# power_dist.net
KiCad netlist of a schematic drawn in EAGLE
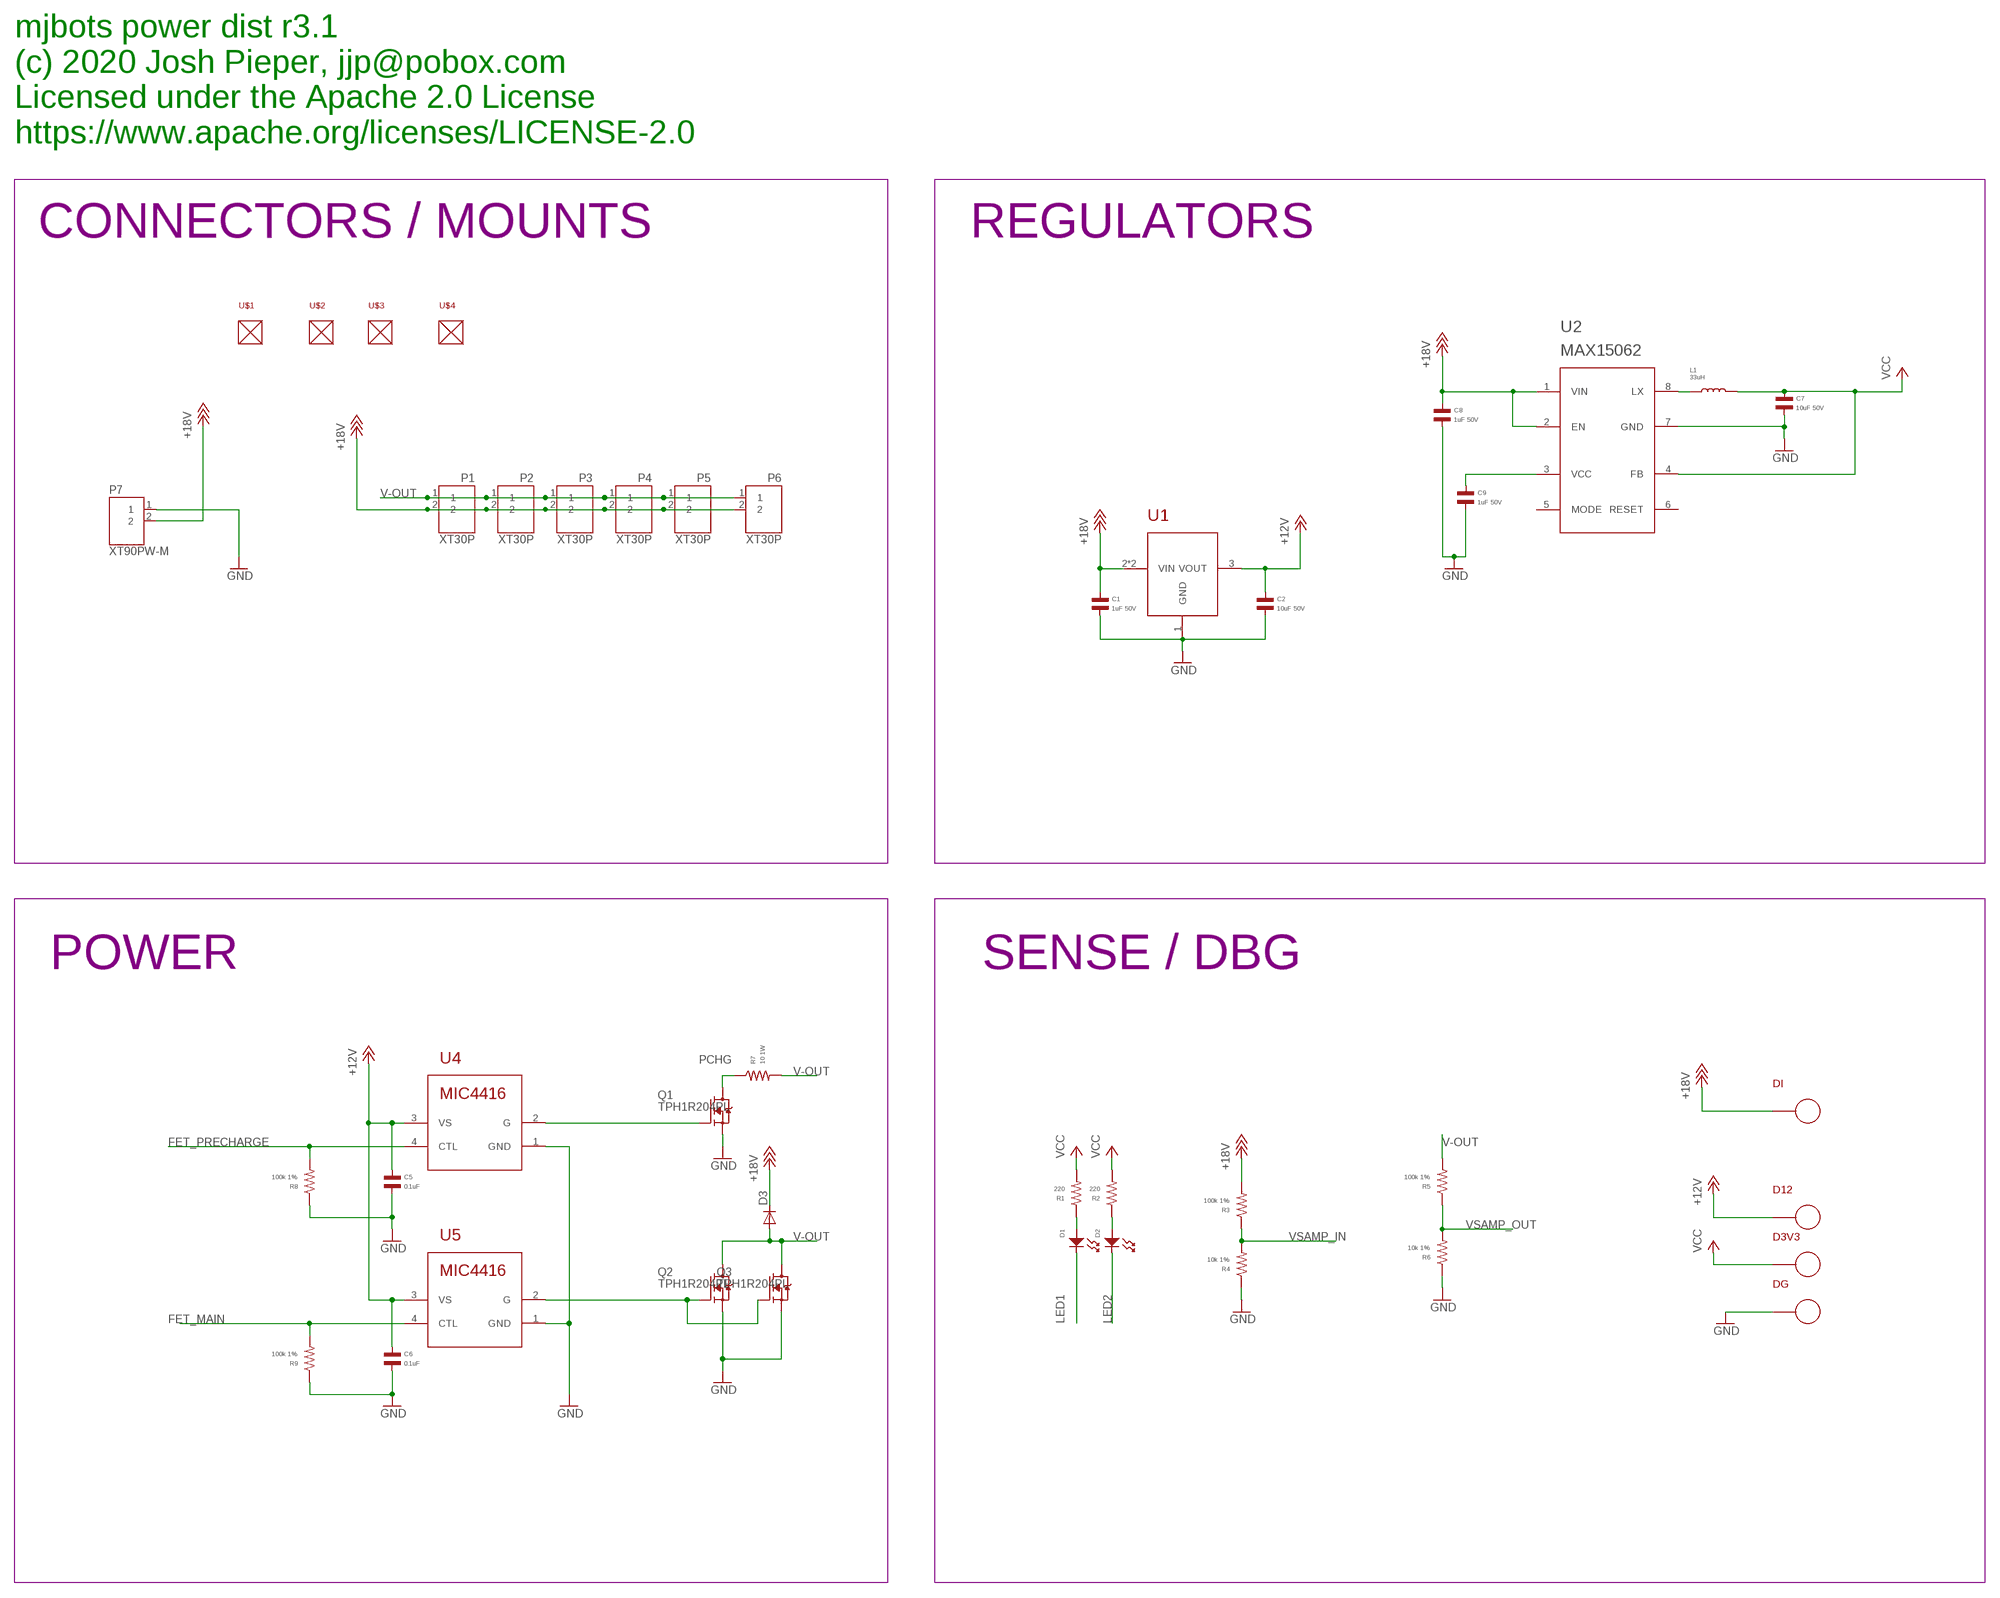
[diagram p0: schematic, sheet 1, part 1 of 2]
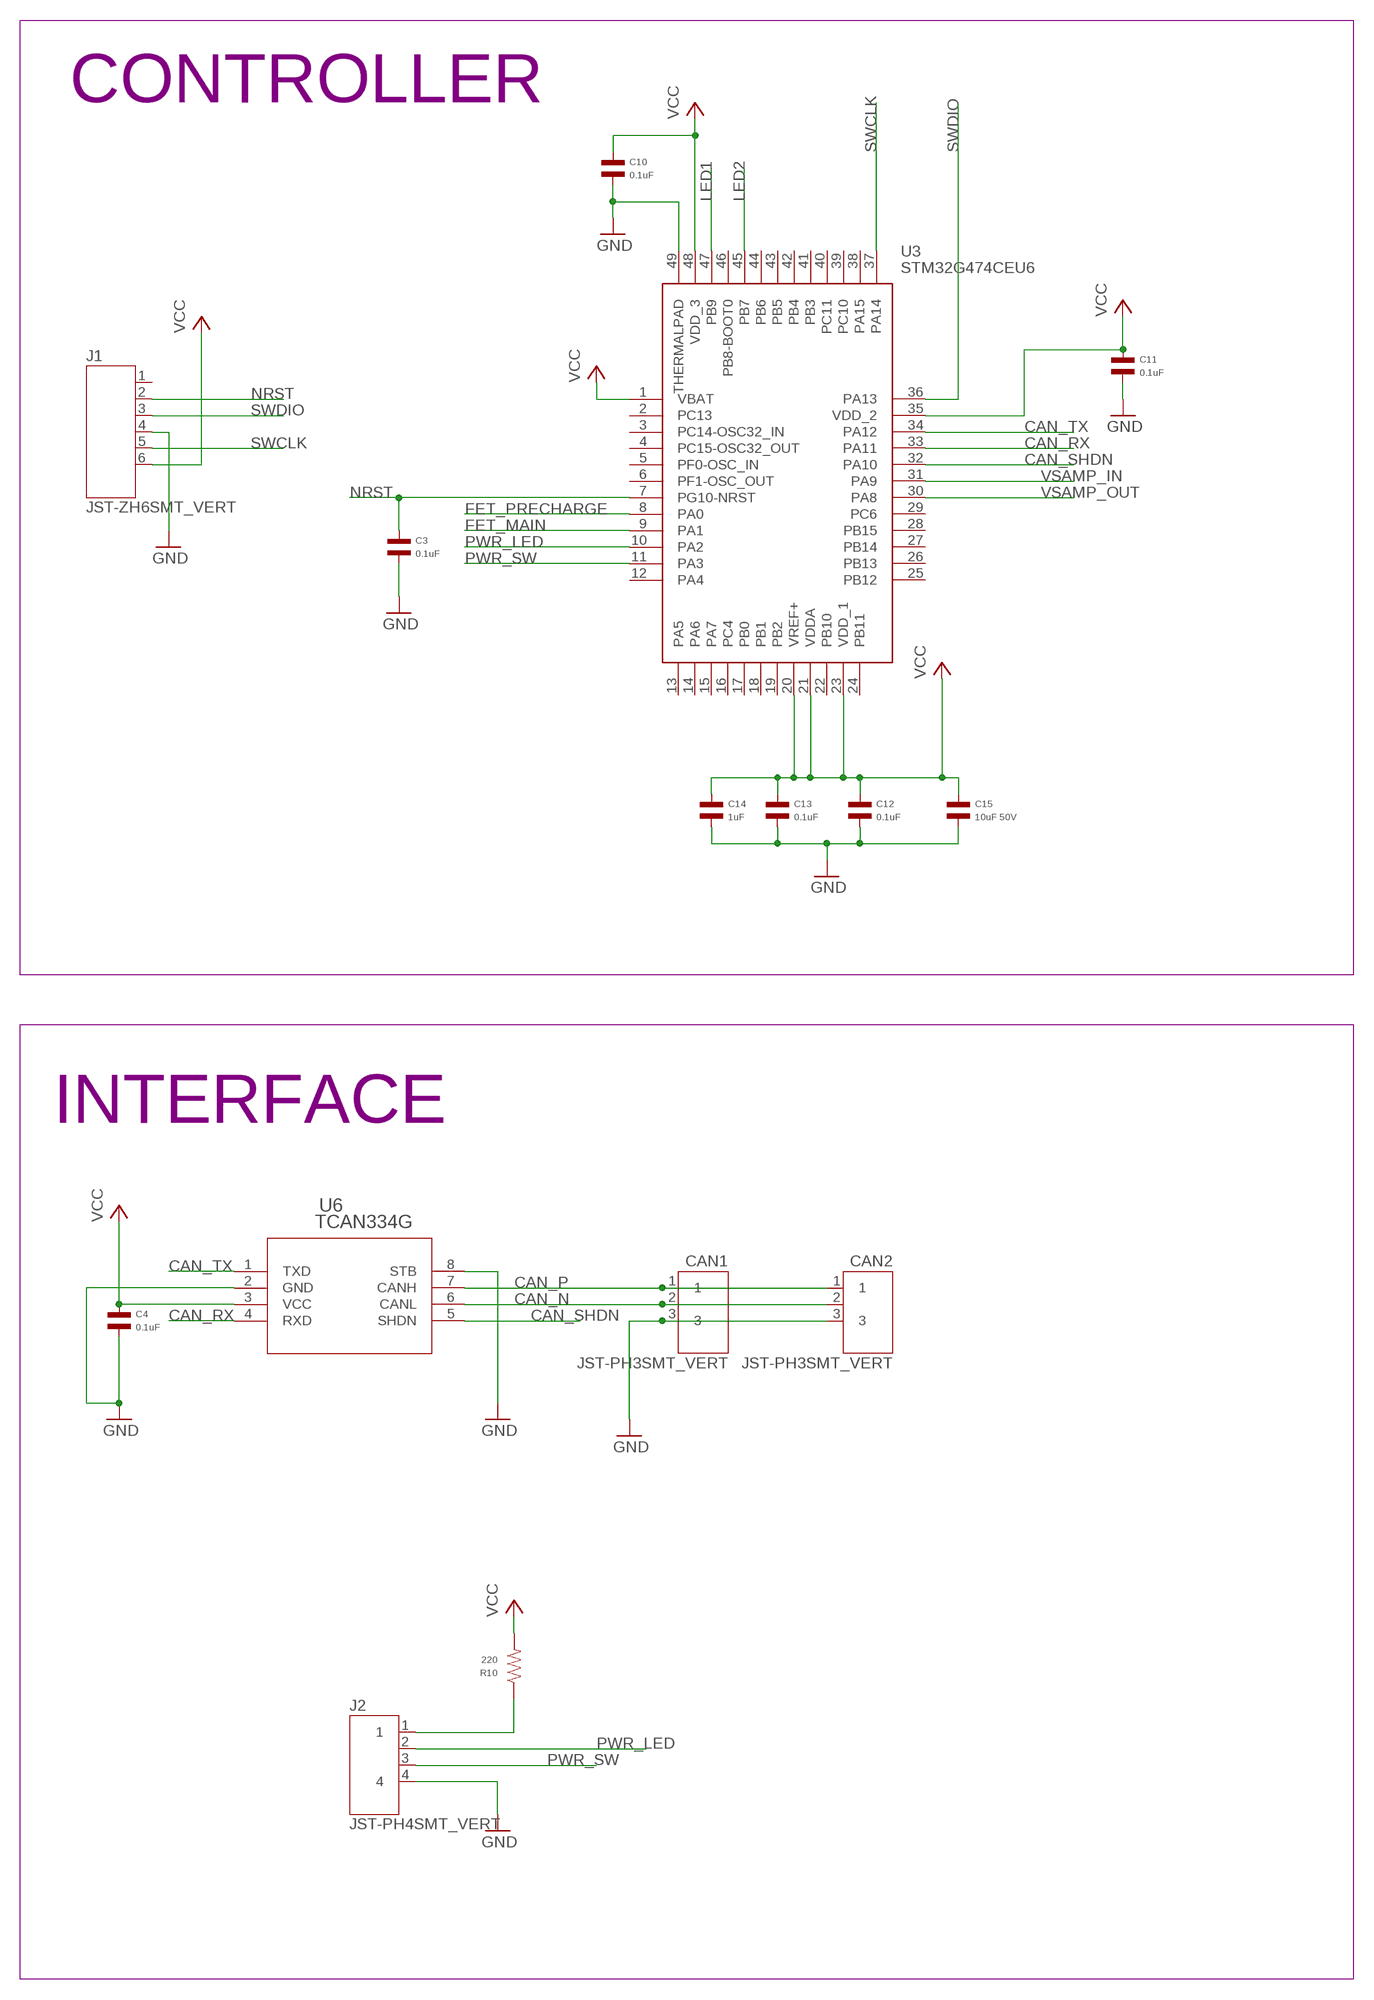
[diagram p1: schematic, sheet 1, part 2 of 2]

(export (version "E")
  (design (tool "Eeschema 10.0.6"))
  (components
    (comp (ref "C1")
      (value "1uF 50V")
      (footprint "eagle-import:C0603")
      (fields (field (name "MF") "SAMSUNG") (field (name "MPN") "CL10A105KB8NNNC"))
      (libsource (lib "eagle-import") (part "CAPACITOR_NP_0603"))
    )
    (comp (ref "C2")
      (value "10uF 50V")
      (footprint "eagle-import:C1206")
      (fields (field (name "MF") "TDK") (field (name "MPN") "C3216X7R1H106K160AE"))
      (libsource (lib "eagle-import") (part "CAPACITOR_NP_1206"))
    )
    (comp (ref "C3")
      (value "0.1uF")
      (footprint "eagle-import:C0402")
      (fields (field (name "HOUSEPART") "1") (field (name "MPN") "MF-CAP-0402-0.1uF"))
      (libsource (lib "eagle-import") (part "CAPACITOR_NP_0402"))
    )
    (comp (ref "C4")
      (value "0.1uF")
      (footprint "eagle-import:C0402")
      (fields (field (name "HOUSEPART") "1") (field (name "MPN") "MF-CAP-0402-0.1uF"))
      (libsource (lib "eagle-import") (part "CAPACITOR_NP_0402"))
    )
    (comp (ref "C5")
      (value "0.1uF")
      (footprint "eagle-import:C0402")
      (fields (field (name "HOUSEPART") "1") (field (name "MPN") "MF-CAP-0402-0.1uF"))
      (libsource (lib "eagle-import") (part "CAPACITOR_NP_0402"))
    )
    (comp (ref "C6")
      (value "0.1uF")
      (footprint "eagle-import:C0402")
      (fields (field (name "HOUSEPART") "1") (field (name "MPN") "MF-CAP-0402-0.1uF"))
      (libsource (lib "eagle-import") (part "CAPACITOR_NP_0402"))
    )
    (comp (ref "C7")
      (value "10uF 50V")
      (footprint "eagle-import:C1206")
      (fields (field (name "MF") "TDK") (field (name "MPN") "C3216X7R1H106K160AE"))
      (libsource (lib "eagle-import") (part "CAPACITOR_NP_1206"))
    )
    (comp (ref "C8")
      (value "1uF 50V")
      (footprint "eagle-import:C0603")
      (fields (field (name "MF") "SAMSUNG") (field (name "MPN") "CL10A105KB8NNNC"))
      (libsource (lib "eagle-import") (part "CAPACITOR_NP_0603"))
    )
    (comp (ref "C9")
      (value "1uF 50V")
      (footprint "eagle-import:C0603")
      (fields (field (name "MF") "SAMSUNG") (field (name "MPN") "CL10A105KB8NNNC"))
      (libsource (lib "eagle-import") (part "CAPACITOR_NP_0603"))
    )
    (comp (ref "C10")
      (value "0.1uF")
      (footprint "eagle-import:C0402")
      (fields (field (name "HOUSEPART") "1") (field (name "MPN") "MF-CAP-0402-0.1uF"))
      (libsource (lib "eagle-import") (part "CAPACITOR_NP_0402"))
    )
    (comp (ref "C11")
      (value "0.1uF")
      (footprint "eagle-import:C0402")
      (fields (field (name "HOUSEPART") "1") (field (name "MPN") "MF-CAP-0402-0.1uF"))
      (libsource (lib "eagle-import") (part "CAPACITOR_NP_0402"))
    )
    (comp (ref "C12")
      (value "0.1uF")
      (footprint "eagle-import:C0402")
      (fields (field (name "HOUSEPART") "1") (field (name "MPN") "MF-CAP-0402-0.1uF"))
      (libsource (lib "eagle-import") (part "CAPACITOR_NP_0402"))
    )
    (comp (ref "C13")
      (value "0.1uF")
      (footprint "eagle-import:C0402")
      (fields (field (name "HOUSEPART") "1") (field (name "MPN") "MF-CAP-0402-0.1uF"))
      (libsource (lib "eagle-import") (part "CAPACITOR_NP_0402"))
    )
    (comp (ref "C14")
      (value "1uF")
      (footprint "eagle-import:C0402")
      (fields (field (name "HOUSEPART") "1") (field (name "MPN") "MF-CAP-0402-1uF"))
      (libsource (lib "eagle-import") (part "CAPACITOR_NP_0402"))
    )
    (comp (ref "C15")
      (value "10uF 50V")
      (footprint "eagle-import:C1206")
      (fields (field (name "MF") "TDK") (field (name "MPN") "C3216X7R1H106K160AE"))
      (libsource (lib "eagle-import") (part "CAPACITOR_NP_1206"))
    )
    (comp (ref "CAN1")
      (value "JST-PH3SMT_VERT")
      (footprint "eagle-import:JST_B3B_PH-SM4-TB(LF)(SN)")
      (fields (field (name "MF") "JST") (field (name "MPN") "B3B-PH-SM4-TB(LF)(SN)"))
      (libsource (lib "eagle-import") (part "JST-PH3SMT_VERT"))
    )
    (comp (ref "CAN2")
      (value "JST-PH3SMT_VERT")
      (footprint "eagle-import:JST_B3B_PH-SM4-TB(LF)(SN)")
      (fields (field (name "MF") "JST") (field (name "MPN") "B3B-PH-SM4-TB(LF)(SN)"))
      (libsource (lib "eagle-import") (part "JST-PH3SMT_VERT"))
    )
    (comp (ref "D1")
      (value "LED_SINGLE-0603")
      (footprint "eagle-import:LED0603")
      (fields
        (field (name "HOUSEPART") "NO")
        (field (name "HOUSEPART_1") "1")
        (field (name "MPN") "MF-LED-0603-RED")
      )
      (libsource (lib "eagle-import") (part "LED_SINGLE-0603"))
    )
    (comp (ref "D2")
      (value "LED_SINGLE-0603")
      (footprint "eagle-import:LED0603")
      (fields
        (field (name "HOUSEPART") "NO")
        (field (name "HOUSEPART_1") "1")
        (field (name "MPN") "MF-LED-0603-RED")
      )
      (libsource (lib "eagle-import") (part "LED_SINGLE-0603"))
    )
    (comp (ref "D3")
      (value "DIODE-")
      (footprint "eagle-import:DO-214AB")
      (fields (field (name "MF") "MICRO COMMERCIAL") (field (name "MPN") "SK510L-TP"))
      (libsource (lib "eagle-import") (part "DIODE-"))
    )
    (comp (ref "D3V3")
      (value "PAD24AWG_PAD")
      (footprint "eagle-import:24AWG_PAD")
      (libsource (lib "eagle-import") (part "PAD24AWG_PAD"))
    )
    (comp (ref "D12")
      (value "PAD24AWG_PAD")
      (footprint "eagle-import:24AWG_PAD")
      (libsource (lib "eagle-import") (part "PAD24AWG_PAD"))
    )
    (comp (ref "DG")
      (value "PAD24AWG_PAD")
      (footprint "eagle-import:24AWG_PAD")
      (libsource (lib "eagle-import") (part "PAD24AWG_PAD"))
    )
    (comp (ref "DI")
      (value "PAD24AWG_PAD")
      (footprint "eagle-import:24AWG_PAD")
      (libsource (lib "eagle-import") (part "PAD24AWG_PAD"))
    )
    (comp (ref "J1")
      (value "JST-ZH6SMT_VERT")
      (footprint "eagle-import:JST_B6B-ZR-SM4-TF(LF)(SN)")
      (fields (field (name "MF") "JST") (field (name "MPN") "B6B-ZR-SM4-TF(LF)(SN)"))
      (libsource (lib "eagle-import") (part "JST-ZH6SMT_VERT"))
    )
    (comp (ref "J2")
      (value "JST-PH4SMT_VERT")
      (footprint "eagle-import:JST_B4B_PH-SM4-TB(LF)(SN)")
      (fields (field (name "MF") "JST") (field (name "MPN") "B4B-PH-SM4-TB(LF)(SN)"))
      (libsource (lib "eagle-import") (part "JST-PH4SMT_VERT"))
    )
    (comp (ref "L1")
      (value "33uH")
      (footprint "eagle-import:L1210")
      (fields (field (name "MF") "TDK") (field (name "MPN") "NLFV32T-330K-EF") (field (name "POPULATE") "1"))
      (libsource (lib "eagle-import") (part "INDUCTOR_1210"))
    )
    (comp (ref "P1")
      (value "XT30P")
      (footprint "eagle-import:XT30P")
      (libsource (lib "eagle-import") (part "XT30P"))
    )
    (comp (ref "P2")
      (value "XT30P")
      (footprint "eagle-import:XT30P")
      (libsource (lib "eagle-import") (part "XT30P"))
    )
    (comp (ref "P3")
      (value "XT30P")
      (footprint "eagle-import:XT30P")
      (libsource (lib "eagle-import") (part "XT30P"))
    )
    (comp (ref "P4")
      (value "XT30P")
      (footprint "eagle-import:XT30P")
      (libsource (lib "eagle-import") (part "XT30P"))
    )
    (comp (ref "P5")
      (value "XT30P")
      (footprint "eagle-import:XT30P")
      (libsource (lib "eagle-import") (part "XT30P"))
    )
    (comp (ref "P6")
      (value "XT30P")
      (footprint "eagle-import:XT30P")
      (libsource (lib "eagle-import") (part "XT30P"))
    )
    (comp (ref "P7")
      (value "XT90PW-M")
      (footprint "eagle-import:XT90PW-M")
      (libsource (lib "eagle-import") (part "XT90PW-M"))
    )
    (comp (ref "Q1")
      (value "TPH1R204PL")
      (footprint "eagle-import:SOP_ADVANCE")
      (fields (field (name "MF") "Toshiba") (field (name "MPN") "TPH1R204PL,L1Q"))
      (libsource (lib "eagle-import") (part "TPH1R204PL"))
    )
    (comp (ref "Q2")
      (value "TPH1R204PL")
      (footprint "eagle-import:SOP_ADVANCE")
      (fields (field (name "MF") "Toshiba") (field (name "MPN") "TPH1R204PL,L1Q"))
      (libsource (lib "eagle-import") (part "TPH1R204PL"))
    )
    (comp (ref "Q3")
      (value "TPH1R204PL")
      (footprint "eagle-import:SOP_ADVANCE")
      (fields (field (name "MF") "Toshiba") (field (name "MPN") "TPH1R204PL,L1Q"))
      (libsource (lib "eagle-import") (part "TPH1R204PL"))
    )
    (comp (ref "R1")
      (value "220")
      (footprint "eagle-import:R0603")
      (fields (field (name "HOUSEPART") "1") (field (name "MPN") "MF-RES-0603-220"))
      (libsource (lib "eagle-import") (part "RESISTOR_0603"))
    )
    (comp (ref "R2")
      (value "220")
      (footprint "eagle-import:R0603")
      (fields (field (name "HOUSEPART") "1") (field (name "MPN") "MF-RES-0603-220"))
      (libsource (lib "eagle-import") (part "RESISTOR_0603"))
    )
    (comp (ref "R3")
      (value "100k 1%")
      (footprint "eagle-import:R0603")
      (fields (field (name "MF") "VISHAY") (field (name "MPN") "CRCW0603100KFKEA"))
      (libsource (lib "eagle-import") (part "RESISTOR_0603"))
    )
    (comp (ref "R4")
      (value "10k 1%")
      (footprint "eagle-import:R0603")
      (fields (field (name "MF") "PANASONIC") (field (name "MPN") "ERJ-3EKF1002V"))
      (libsource (lib "eagle-import") (part "RESISTOR_0603"))
    )
    (comp (ref "R5")
      (value "100k 1%")
      (footprint "eagle-import:R0603")
      (fields (field (name "MF") "VISHAY") (field (name "MPN") "CRCW0603100KFKEA"))
      (libsource (lib "eagle-import") (part "RESISTOR_0603"))
    )
    (comp (ref "R6")
      (value "10k 1%")
      (footprint "eagle-import:R0603")
      (fields (field (name "MF") "PANASONIC") (field (name "MPN") "ERJ-3EKF1002V"))
      (libsource (lib "eagle-import") (part "RESISTOR_0603"))
    )
    (comp (ref "R7")
      (value "10 1W")
      (footprint "eagle-import:R1206")
      (fields (field (name "MF") "Susumu") (field (name "MPN") "HRG3216Q-10R0-D-T1"))
      (libsource (lib "eagle-import") (part "RESISTOR_1206"))
    )
    (comp (ref "R8")
      (value "100k 1%")
      (footprint "eagle-import:R0603")
      (fields (field (name "MF") "VISHAY") (field (name "MPN") "CRCW0603100KFKEA"))
      (libsource (lib "eagle-import") (part "RESISTOR_0603"))
    )
    (comp (ref "R9")
      (value "100k 1%")
      (footprint "eagle-import:R0603")
      (fields (field (name "MF") "VISHAY") (field (name "MPN") "CRCW0603100KFKEA"))
      (libsource (lib "eagle-import") (part "RESISTOR_0603"))
    )
    (comp (ref "R10")
      (value "220")
      (footprint "eagle-import:R0603")
      (fields (field (name "HOUSEPART") "1") (field (name "MPN") "MF-RES-0603-220"))
      (libsource (lib "eagle-import") (part "RESISTOR_0603"))
    )
    (comp (ref "U$1")
      (value "MOUNT")
      (footprint "eagle-import:M2.5MOUNT")
      (libsource (lib "eagle-import") (part "MOUNT"))
    )
    (comp (ref "U$2")
      (value "MOUNT")
      (footprint "eagle-import:M2.5MOUNT")
      (libsource (lib "eagle-import") (part "MOUNT"))
    )
    (comp (ref "U$3")
      (value "MOUNT")
      (footprint "eagle-import:M2.5MOUNT")
      (libsource (lib "eagle-import") (part "MOUNT"))
    )
    (comp (ref "U$4")
      (value "MOUNT")
      (footprint "eagle-import:M2.5MOUNT")
      (libsource (lib "eagle-import") (part "MOUNT"))
    )
    (comp (ref "U1")
      (value "ZXTR2012Z")
      (footprint "eagle-import:SOT89")
      (fields (field (name "MF") "DIODES INC") (field (name "MPN") "ZXTR2012Z-13"))
      (libsource (lib "eagle-import") (part "ZXTR2012Z"))
    )
    (comp (ref "U2")
      (value "MAX150628TDFN")
      (footprint "eagle-import:8TDFN")
      (fields (field (name "MF") "MAXIM") (field (name "MPN") "MAX15062AATA+T"))
      (libsource (lib "eagle-import") (part "MAX150628TDFN"))
    )
    (comp (ref "U3")
      (value "STM32G474CEU6")
      (footprint "eagle-import:QFN50P700X700X60-49N")
      (fields (field (name "MOUSER_PART_NUMBER") "511-STM32G474CEU6") (field (name "MF") "ST"))
      (libsource (lib "eagle-import") (part "STM32G474CEU6"))
    )
    (comp (ref "U4")
      (value "MIC4416")
      (footprint "eagle-import:SOT143")
      (fields (field (name "MF") "MICROCHIP") (field (name "MPN") "MIC4416YM4-TR"))
      (libsource (lib "eagle-import") (part "MIC4416"))
    )
    (comp (ref "U5")
      (value "MIC4416")
      (footprint "eagle-import:SOT143")
      (fields (field (name "MF") "MICROCHIP") (field (name "MPN") "MIC4416YM4-TR"))
      (libsource (lib "eagle-import") (part "MIC4416"))
    )
    (comp (ref "U6")
      (value "TCAN334G")
      (footprint "eagle-import:SOIC8")
      (fields (field (name "MF") "Analog") (field (name "MPN") "LTC2875IS8"))
      (libsource (lib "eagle-import") (part "TCAN334G"))
    )
  )
  (nets
    (net (code "1") (name "+12V") (class "Default")
      (node (ref "C2") (pin "P$1") (pinfunction "P$1_P$1") (pintype "passive"))
      (node (ref "C5") (pin "P$1") (pinfunction "P$1_P$1") (pintype "passive"))
      (node (ref "C6") (pin "P$1") (pinfunction "P$1_P$1") (pintype "passive"))
      (node (ref "D12") (pin "P$1") (pinfunction "P$1_P$1") (pintype "bidirectional"))
      (node (ref "U1") (pin "3") (pinfunction "VOUT_3") (pintype "bidirectional"))
      (node (ref "U4") (pin "3") (pinfunction "VS_3") (pintype "bidirectional"))
      (node (ref "U5") (pin "3") (pinfunction "VS_3") (pintype "bidirectional"))
    )
    (net (code "2") (name "+18V") (class "Default")
      (node (ref "C1") (pin "P$1") (pinfunction "P$1_P$1") (pintype "passive"))
      (node (ref "C8") (pin "P$1") (pinfunction "P$1_P$1") (pintype "passive"))
      (node (ref "D3") (pin "C") (pinfunction "C_C") (pintype "passive"))
      (node (ref "DI") (pin "P$1") (pinfunction "P$1_P$1") (pintype "bidirectional"))
      (node (ref "P1") (pin "2") (pinfunction "2_2") (pintype "passive"))
      (node (ref "P2") (pin "2") (pinfunction "2_2") (pintype "passive"))
      (node (ref "P3") (pin "2") (pinfunction "2_2") (pintype "passive"))
      (node (ref "P4") (pin "2") (pinfunction "2_2") (pintype "passive"))
      (node (ref "P5") (pin "2") (pinfunction "2_2") (pintype "passive"))
      (node (ref "P6") (pin "2") (pinfunction "2_2") (pintype "passive"))
      (node (ref "P7") (pin "2") (pinfunction "2_2") (pintype "passive"))
      (node (ref "R3") (pin "P$2") (pinfunction "P$2_P$2") (pintype "passive"))
      (node (ref "U1") (pin "2") (pinfunction "VIN_2") (pintype "bidirectional"))
      (node (ref "U1") (pin "PAD") (pinfunction "VIN_PAD") (pintype "bidirectional"))
      (node (ref "U2") (pin "1") (pinfunction "VIN_1") (pintype "passive"))
      (node (ref "U2") (pin "2") (pinfunction "EN_2") (pintype "passive"))
    )
    (net (code "3") (name "/CAN_N") (class "Default")
      (node (ref "CAN1") (pin "2") (pinfunction "2_2") (pintype "passive"))
      (node (ref "CAN2") (pin "2") (pinfunction "2_2") (pintype "passive"))
      (node (ref "U6") (pin "6") (pinfunction "CANL_6") (pintype "bidirectional"))
    )
    (net (code "4") (name "/CAN_P") (class "Default")
      (node (ref "CAN1") (pin "1") (pinfunction "1_1") (pintype "passive"))
      (node (ref "CAN2") (pin "1") (pinfunction "1_1") (pintype "passive"))
      (node (ref "U6") (pin "7") (pinfunction "CANH_7") (pintype "bidirectional"))
    )
    (net (code "5") (name "/CAN_RX") (class "Default")
      (node (ref "U3") (pin "33") (pinfunction "PA11_33") (pintype "bidirectional"))
      (node (ref "U6") (pin "4") (pinfunction "RXD_4") (pintype "output"))
    )
    (net (code "6") (name "/CAN_SHDN") (class "Default")
      (node (ref "U3") (pin "32") (pinfunction "PA10_32") (pintype "bidirectional"))
      (node (ref "U6") (pin "5") (pinfunction "SHDN_5") (pintype "input"))
    )
    (net (code "7") (name "/CAN_TX") (class "Default")
      (node (ref "U3") (pin "34") (pinfunction "PA12_34") (pintype "bidirectional"))
      (node (ref "U6") (pin "1") (pinfunction "TXD_1") (pintype "input"))
    )
    (net (code "8") (name "/FET_MAIN") (class "Default")
      (node (ref "R9") (pin "P$2") (pinfunction "P$2_P$2") (pintype "passive"))
      (node (ref "U3") (pin "9") (pinfunction "PA1_9") (pintype "bidirectional"))
      (node (ref "U5") (pin "4") (pinfunction "CTL_4") (pintype "bidirectional"))
    )
    (net (code "9") (name "/FET_PRECHARGE") (class "Default")
      (node (ref "R8") (pin "P$2") (pinfunction "P$2_P$2") (pintype "passive"))
      (node (ref "U3") (pin "8") (pinfunction "PA0_8") (pintype "bidirectional"))
      (node (ref "U4") (pin "4") (pinfunction "CTL_4") (pintype "bidirectional"))
    )
    (net (code "10") (name "/LED1") (class "Default")
      (node (ref "D1") (pin "CATHODE") (pinfunction "CATHODE_CATHODE") (pintype "power_in"))
      (node (ref "U3") (pin "47") (pinfunction "PB9_47") (pintype "bidirectional"))
    )
    (net (code "11") (name "/LED2") (class "Default")
      (node (ref "D2") (pin "CATHODE") (pinfunction "CATHODE_CATHODE") (pintype "power_in"))
      (node (ref "U3") (pin "45") (pinfunction "PB7_45") (pintype "bidirectional"))
    )
    (net (code "12") (name "/NRST") (class "Default")
      (node (ref "C3") (pin "P$1") (pinfunction "P$1_P$1") (pintype "passive"))
      (node (ref "J1") (pin "2") (pinfunction "2_2") (pintype "passive"))
      (node (ref "U3") (pin "7") (pinfunction "PG10-NRST_7") (pintype "bidirectional"))
    )
    (net (code "13") (name "/PCHG") (class "Default")
      (node (ref "Q1") (pin "5") (pinfunction "D_5") (pintype "passive"))
      (node (ref "Q1") (pin "6") (pinfunction "D_6") (pintype "passive"))
      (node (ref "Q1") (pin "7") (pinfunction "D_7") (pintype "passive"))
      (node (ref "Q1") (pin "8") (pinfunction "D_8") (pintype "passive"))
      (node (ref "Q1") (pin "PAD") (pinfunction "D_PAD") (pintype "passive"))
      (node (ref "R7") (pin "P$1") (pinfunction "P$1_P$1") (pintype "passive"))
    )
    (net (code "14") (name "/PWR_LED") (class "Default")
      (node (ref "J2") (pin "2") (pinfunction "2_2") (pintype "passive"))
      (node (ref "U3") (pin "10") (pinfunction "PA2_10") (pintype "bidirectional"))
    )
    (net (code "15") (name "/PWR_SW") (class "Default")
      (node (ref "J2") (pin "3") (pinfunction "3_3") (pintype "passive"))
      (node (ref "U3") (pin "11") (pinfunction "PA3_11") (pintype "bidirectional"))
    )
    (net (code "16") (name "/SWCLK") (class "Default")
      (node (ref "J1") (pin "5") (pinfunction "5_5") (pintype "passive"))
      (node (ref "U3") (pin "37") (pinfunction "PA14_37") (pintype "bidirectional"))
    )
    (net (code "17") (name "/SWDIO") (class "Default")
      (node (ref "J1") (pin "3") (pinfunction "3_3") (pintype "passive"))
      (node (ref "U3") (pin "36") (pinfunction "PA13_36") (pintype "bidirectional"))
    )
    (net (code "18") (name "/V-OUT") (class "Default")
      (node (ref "D3") (pin "A") (pinfunction "A_A") (pintype "passive"))
      (node (ref "P1") (pin "1") (pinfunction "1_1") (pintype "passive"))
      (node (ref "P2") (pin "1") (pinfunction "1_1") (pintype "passive"))
      (node (ref "P3") (pin "1") (pinfunction "1_1") (pintype "passive"))
      (node (ref "P4") (pin "1") (pinfunction "1_1") (pintype "passive"))
      (node (ref "P5") (pin "1") (pinfunction "1_1") (pintype "passive"))
      (node (ref "P6") (pin "1") (pinfunction "1_1") (pintype "passive"))
      (node (ref "Q2") (pin "5") (pinfunction "D_5") (pintype "passive"))
      (node (ref "Q2") (pin "6") (pinfunction "D_6") (pintype "passive"))
      (node (ref "Q2") (pin "7") (pinfunction "D_7") (pintype "passive"))
      (node (ref "Q2") (pin "8") (pinfunction "D_8") (pintype "passive"))
      (node (ref "Q2") (pin "PAD") (pinfunction "D_PAD") (pintype "passive"))
      (node (ref "Q3") (pin "5") (pinfunction "D_5") (pintype "passive"))
      (node (ref "Q3") (pin "6") (pinfunction "D_6") (pintype "passive"))
      (node (ref "Q3") (pin "7") (pinfunction "D_7") (pintype "passive"))
      (node (ref "Q3") (pin "8") (pinfunction "D_8") (pintype "passive"))
      (node (ref "Q3") (pin "PAD") (pinfunction "D_PAD") (pintype "passive"))
      (node (ref "R5") (pin "P$2") (pinfunction "P$2_P$2") (pintype "passive"))
      (node (ref "R7") (pin "P$2") (pinfunction "P$2_P$2") (pintype "passive"))
    )
    (net (code "19") (name "/VSAMP_IN") (class "Default")
      (node (ref "R3") (pin "P$1") (pinfunction "P$1_P$1") (pintype "passive"))
      (node (ref "R4") (pin "P$2") (pinfunction "P$2_P$2") (pintype "passive"))
      (node (ref "U3") (pin "31") (pinfunction "PA9_31") (pintype "bidirectional"))
    )
    (net (code "20") (name "/VSAMP_OUT") (class "Default")
      (node (ref "R5") (pin "P$1") (pinfunction "P$1_P$1") (pintype "passive"))
      (node (ref "R6") (pin "P$2") (pinfunction "P$2_P$2") (pintype "passive"))
      (node (ref "U3") (pin "30") (pinfunction "PA8_30") (pintype "bidirectional"))
    )
    (net (code "21") (name "GND") (class "Default")
      (node (ref "C1") (pin "P$2") (pinfunction "P$2_P$2") (pintype "passive"))
      (node (ref "C10") (pin "P$2") (pinfunction "P$2_P$2") (pintype "passive"))
      (node (ref "C11") (pin "P$2") (pinfunction "P$2_P$2") (pintype "passive"))
      (node (ref "C12") (pin "P$2") (pinfunction "P$2_P$2") (pintype "passive"))
      (node (ref "C13") (pin "P$2") (pinfunction "P$2_P$2") (pintype "passive"))
      (node (ref "C14") (pin "P$2") (pinfunction "P$2_P$2") (pintype "passive"))
      (node (ref "C15") (pin "P$2") (pinfunction "P$2_P$2") (pintype "passive"))
      (node (ref "C2") (pin "P$2") (pinfunction "P$2_P$2") (pintype "passive"))
      (node (ref "C3") (pin "P$2") (pinfunction "P$2_P$2") (pintype "passive"))
      (node (ref "C4") (pin "P$2") (pinfunction "P$2_P$2") (pintype "passive"))
      (node (ref "C5") (pin "P$2") (pinfunction "P$2_P$2") (pintype "passive"))
      (node (ref "C6") (pin "P$2") (pinfunction "P$2_P$2") (pintype "passive"))
      (node (ref "C7") (pin "P$2") (pinfunction "P$2_P$2") (pintype "passive"))
      (node (ref "C8") (pin "P$2") (pinfunction "P$2_P$2") (pintype "passive"))
      (node (ref "C9") (pin "P$2") (pinfunction "P$2_P$2") (pintype "passive"))
      (node (ref "CAN1") (pin "3") (pinfunction "3_3") (pintype "passive"))
      (node (ref "CAN2") (pin "3") (pinfunction "3_3") (pintype "passive"))
      (node (ref "DG") (pin "P$1") (pinfunction "P$1_P$1") (pintype "bidirectional"))
      (node (ref "J1") (pin "4") (pinfunction "4_4") (pintype "passive"))
      (node (ref "J2") (pin "4") (pinfunction "4_4") (pintype "passive"))
      (node (ref "P7") (pin "1") (pinfunction "1_1") (pintype "passive"))
      (node (ref "Q1") (pin "1") (pinfunction "S_1") (pintype "passive"))
      (node (ref "Q1") (pin "2") (pinfunction "S_2") (pintype "passive"))
      (node (ref "Q1") (pin "3") (pinfunction "S_3") (pintype "passive"))
      (node (ref "Q2") (pin "1") (pinfunction "S_1") (pintype "passive"))
      (node (ref "Q2") (pin "2") (pinfunction "S_2") (pintype "passive"))
      (node (ref "Q2") (pin "3") (pinfunction "S_3") (pintype "passive"))
      (node (ref "Q3") (pin "1") (pinfunction "S_1") (pintype "passive"))
      (node (ref "Q3") (pin "2") (pinfunction "S_2") (pintype "passive"))
      (node (ref "Q3") (pin "3") (pinfunction "S_3") (pintype "passive"))
      (node (ref "R4") (pin "P$1") (pinfunction "P$1_P$1") (pintype "passive"))
      (node (ref "R6") (pin "P$1") (pinfunction "P$1_P$1") (pintype "passive"))
      (node (ref "R8") (pin "P$1") (pinfunction "P$1_P$1") (pintype "passive"))
      (node (ref "R9") (pin "P$1") (pinfunction "P$1_P$1") (pintype "passive"))
      (node (ref "U1") (pin "1") (pinfunction "GND_1") (pintype "bidirectional"))
      (node (ref "U2") (pin "7") (pinfunction "GND_7") (pintype "passive"))
      (node (ref "U3") (pin "49") (pinfunction "THERMALPAD_49") (pintype "bidirectional"))
      (node (ref "U4") (pin "1") (pinfunction "GND_1") (pintype "bidirectional"))
      (node (ref "U5") (pin "1") (pinfunction "GND_1") (pintype "bidirectional"))
      (node (ref "U6") (pin "2") (pinfunction "GND_2") (pintype "power_in"))
      (node (ref "U6") (pin "8") (pinfunction "STB_8") (pintype "input"))
    )
    (net (code "22") (name "Net-(D1-PadANODE)") (class "Default")
      (node (ref "D1") (pin "ANODE") (pinfunction "ANODE_ANODE") (pintype "power_in"))
      (node (ref "R1") (pin "P$1") (pinfunction "P$1_P$1") (pintype "passive"))
    )
    (net (code "23") (name "Net-(D2-PadANODE)") (class "Default")
      (node (ref "D2") (pin "ANODE") (pinfunction "ANODE_ANODE") (pintype "power_in"))
      (node (ref "R2") (pin "P$1") (pinfunction "P$1_P$1") (pintype "passive"))
    )
    (net (code "24") (name "Net-(J2-Pad1)") (class "Default")
      (node (ref "J2") (pin "1") (pinfunction "1_1") (pintype "passive"))
      (node (ref "R10") (pin "P$1") (pinfunction "P$1_P$1") (pintype "passive"))
    )
    (net (code "25") (name "Net-(Q1-G)") (class "Default")
      (node (ref "Q1") (pin "4") (pinfunction "G_4") (pintype "passive"))
      (node (ref "U4") (pin "2") (pinfunction "G_2") (pintype "bidirectional"))
    )
    (net (code "26") (name "Net-(Q2-G)") (class "Default")
      (node (ref "Q2") (pin "4") (pinfunction "G_4") (pintype "passive"))
      (node (ref "Q3") (pin "4") (pinfunction "G_4") (pintype "passive"))
      (node (ref "U5") (pin "2") (pinfunction "G_2") (pintype "bidirectional"))
    )
    (net (code "27") (name "Net-(U2-LX)") (class "Default")
      (node (ref "L1") (pin "P$1") (pinfunction "P$1_P$1") (pintype "passive"))
      (node (ref "U2") (pin "8") (pinfunction "LX_8") (pintype "passive"))
    )
    (net (code "28") (name "Net-(U2-VCC)") (class "Default")
      (node (ref "C9") (pin "P$1") (pinfunction "P$1_P$1") (pintype "passive"))
      (node (ref "U2") (pin "3") (pinfunction "VCC_3") (pintype "passive"))
    )
    (net (code "29") (name "VCC") (class "Default")
      (node (ref "C10") (pin "P$1") (pinfunction "P$1_P$1") (pintype "passive"))
      (node (ref "C11") (pin "P$1") (pinfunction "P$1_P$1") (pintype "passive"))
      (node (ref "C12") (pin "P$1") (pinfunction "P$1_P$1") (pintype "passive"))
      (node (ref "C13") (pin "P$1") (pinfunction "P$1_P$1") (pintype "passive"))
      (node (ref "C14") (pin "P$1") (pinfunction "P$1_P$1") (pintype "passive"))
      (node (ref "C15") (pin "P$1") (pinfunction "P$1_P$1") (pintype "passive"))
      (node (ref "C4") (pin "P$1") (pinfunction "P$1_P$1") (pintype "passive"))
      (node (ref "C7") (pin "P$1") (pinfunction "P$1_P$1") (pintype "passive"))
      (node (ref "D3V3") (pin "P$1") (pinfunction "P$1_P$1") (pintype "bidirectional"))
      (node (ref "J1") (pin "6") (pinfunction "6_6") (pintype "passive"))
      (node (ref "L1") (pin "P$2") (pinfunction "P$2_P$2") (pintype "passive"))
      (node (ref "R1") (pin "P$2") (pinfunction "P$2_P$2") (pintype "passive"))
      (node (ref "R10") (pin "P$2") (pinfunction "P$2_P$2") (pintype "passive"))
      (node (ref "R2") (pin "P$2") (pinfunction "P$2_P$2") (pintype "passive"))
      (node (ref "U2") (pin "4") (pinfunction "FB_4") (pintype "passive"))
      (node (ref "U3") (pin "1") (pinfunction "VBAT_1") (pintype "bidirectional"))
      (node (ref "U3") (pin "20") (pinfunction "VREF+_20") (pintype "bidirectional"))
      (node (ref "U3") (pin "21") (pinfunction "VDDA_21") (pintype "bidirectional"))
      (node (ref "U3") (pin "23") (pinfunction "VDD_1_23") (pintype "bidirectional"))
      (node (ref "U3") (pin "35") (pinfunction "VDD_2_35") (pintype "bidirectional"))
      (node (ref "U3") (pin "48") (pinfunction "VDD_3_48") (pintype "bidirectional"))
      (node (ref "U6") (pin "3") (pinfunction "VCC_3") (pintype "power_in"))
    )
    (net (code "30") (name "unconnected-(J1-Pad1)") (class "Default")
      (node (ref "J1") (pin "1") (pinfunction "1_1") (pintype "passive"))
    )
    (net (code "31") (name "unconnected-(U2-MODE-Pad5)") (class "Default")
      (node (ref "U2") (pin "5") (pinfunction "MODE_5") (pintype "passive"))
    )
    (net (code "32") (name "unconnected-(U2-RESET-Pad6)") (class "Default")
      (node (ref "U2") (pin "6") (pinfunction "RESET_6") (pintype "passive"))
    )
    (net (code "33") (name "unconnected-(U3-PA4-Pad12)") (class "Default")
      (node (ref "U3") (pin "12") (pinfunction "PA4_12") (pintype "bidirectional"))
    )
    (net (code "34") (name "unconnected-(U3-PA5-Pad13)") (class "Default")
      (node (ref "U3") (pin "13") (pinfunction "PA5_13") (pintype "bidirectional"))
    )
    (net (code "35") (name "unconnected-(U3-PA6-Pad14)") (class "Default")
      (node (ref "U3") (pin "14") (pinfunction "PA6_14") (pintype "bidirectional"))
    )
    (net (code "36") (name "unconnected-(U3-PA7-Pad15)") (class "Default")
      (node (ref "U3") (pin "15") (pinfunction "PA7_15") (pintype "bidirectional"))
    )
    (net (code "37") (name "unconnected-(U3-PA15-Pad38)") (class "Default")
      (node (ref "U3") (pin "38") (pinfunction "PA15_38") (pintype "bidirectional"))
    )
    (net (code "38") (name "unconnected-(U3-PB0-Pad17)") (class "Default")
      (node (ref "U3") (pin "17") (pinfunction "PB0_17") (pintype "bidirectional"))
    )
    (net (code "39") (name "unconnected-(U3-PB1-Pad18)") (class "Default")
      (node (ref "U3") (pin "18") (pinfunction "PB1_18") (pintype "bidirectional"))
    )
    (net (code "40") (name "unconnected-(U3-PB2-Pad19)") (class "Default")
      (node (ref "U3") (pin "19") (pinfunction "PB2_19") (pintype "bidirectional"))
    )
    (net (code "41") (name "unconnected-(U3-PB3-Pad41)") (class "Default")
      (node (ref "U3") (pin "41") (pinfunction "PB3_41") (pintype "bidirectional"))
    )
    (net (code "42") (name "unconnected-(U3-PB4-Pad42)") (class "Default")
      (node (ref "U3") (pin "42") (pinfunction "PB4_42") (pintype "bidirectional"))
    )
    (net (code "43") (name "unconnected-(U3-PB5-Pad43)") (class "Default")
      (node (ref "U3") (pin "43") (pinfunction "PB5_43") (pintype "bidirectional"))
    )
    (net (code "44") (name "unconnected-(U3-PB6-Pad44)") (class "Default")
      (node (ref "U3") (pin "44") (pinfunction "PB6_44") (pintype "bidirectional"))
    )
    (net (code "45") (name "unconnected-(U3-PB8-BOOT0-Pad46)") (class "Default")
      (node (ref "U3") (pin "46") (pinfunction "PB8-BOOT0_46") (pintype "bidirectional"))
    )
    (net (code "46") (name "unconnected-(U3-PB10-Pad22)") (class "Default")
      (node (ref "U3") (pin "22") (pinfunction "PB10_22") (pintype "bidirectional"))
    )
    (net (code "47") (name "unconnected-(U3-PB11-Pad24)") (class "Default")
      (node (ref "U3") (pin "24") (pinfunction "PB11_24") (pintype "bidirectional"))
    )
    (net (code "48") (name "unconnected-(U3-PB12-Pad25)") (class "Default")
      (node (ref "U3") (pin "25") (pinfunction "PB12_25") (pintype "bidirectional"))
    )
    (net (code "49") (name "unconnected-(U3-PB13-Pad26)") (class "Default")
      (node (ref "U3") (pin "26") (pinfunction "PB13_26") (pintype "bidirectional"))
    )
    (net (code "50") (name "unconnected-(U3-PB14-Pad27)") (class "Default")
      (node (ref "U3") (pin "27") (pinfunction "PB14_27") (pintype "bidirectional"))
    )
    (net (code "51") (name "unconnected-(U3-PB15-Pad28)") (class "Default")
      (node (ref "U3") (pin "28") (pinfunction "PB15_28") (pintype "bidirectional"))
    )
    (net (code "52") (name "unconnected-(U3-PC4-Pad16)") (class "Default")
      (node (ref "U3") (pin "16") (pinfunction "PC4_16") (pintype "bidirectional"))
    )
    (net (code "53") (name "unconnected-(U3-PC6-Pad29)") (class "Default")
      (node (ref "U3") (pin "29") (pinfunction "PC6_29") (pintype "bidirectional"))
    )
    (net (code "54") (name "unconnected-(U3-PC10-Pad39)") (class "Default")
      (node (ref "U3") (pin "39") (pinfunction "PC10_39") (pintype "bidirectional"))
    )
    (net (code "55") (name "unconnected-(U3-PC11-Pad40)") (class "Default")
      (node (ref "U3") (pin "40") (pinfunction "PC11_40") (pintype "bidirectional"))
    )
    (net (code "56") (name "unconnected-(U3-PC13-Pad2)") (class "Default")
      (node (ref "U3") (pin "2") (pinfunction "PC13_2") (pintype "bidirectional"))
    )
    (net (code "57") (name "unconnected-(U3-PC14-OSC32_IN-Pad3)") (class "Default")
      (node (ref "U3") (pin "3") (pinfunction "PC14-OSC32_IN_3") (pintype "bidirectional"))
    )
    (net (code "58") (name "unconnected-(U3-PC15-OSC32_OUT-Pad4)") (class "Default")
      (node (ref "U3") (pin "4") (pinfunction "PC15-OSC32_OUT_4") (pintype "bidirectional"))
    )
    (net (code "59") (name "unconnected-(U3-PF0-OSC_IN-Pad5)") (class "Default")
      (node (ref "U3") (pin "5") (pinfunction "PF0-OSC_IN_5") (pintype "bidirectional"))
    )
    (net (code "60") (name "unconnected-(U3-PF1-OSC_OUT-Pad6)") (class "Default")
      (node (ref "U3") (pin "6") (pinfunction "PF1-OSC_OUT_6") (pintype "bidirectional"))
    )
  )
)
